# SWD.net
KiCad netlist of a schematic drawn in Altium Designer
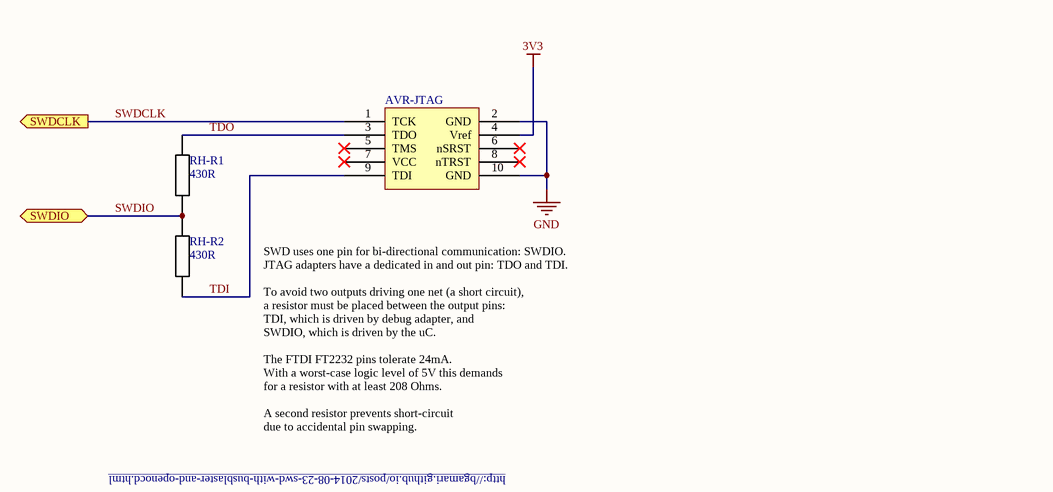
[diagram p0: SWD.SchDoc]

(export (version "E")
  (design (tool "Eeschema 10.0.6"))
  (components
    (comp (ref "AVR-JTAG")
      (value "AVR Style")
      (footprint "Header 2x5 IDC-10S")
      (libsource (lib "Headers") (part "Header JTAG AVR"))
    )
    (comp (ref "RH-R1")
      (value "430R")
      (footprint "R 0805 / 2012")
      (libsource (lib "Core51822-related") (part "Resistor"))
    )
    (comp (ref "RH-R2")
      (value "430R")
      (footprint "R 0805 / 2012")
      (libsource (lib "Core51822-related") (part "Resistor"))
    )
  )
  (nets
    (net (code "1") (name "/SWDCLK") (class "Default")
      (node (ref "AVR-JTAG") (pin "1") (pinfunction "TCK_1") (pintype "passive"))
    )
    (net (code "2") (name "/SWDIO") (class "Default")
      (node (ref "RH-R1") (pin "1") (pinfunction "1_1") (pintype "passive"))
      (node (ref "RH-R2") (pin "2") (pinfunction "2_2") (pintype "passive"))
    )
    (net (code "3") (name "/TDI") (class "Default")
      (node (ref "AVR-JTAG") (pin "9") (pinfunction "TDI_9") (pintype "passive"))
      (node (ref "RH-R2") (pin "1") (pinfunction "1_1") (pintype "passive"))
    )
    (net (code "4") (name "/TDO") (class "Default")
      (node (ref "AVR-JTAG") (pin "3") (pinfunction "TDO_3") (pintype "passive"))
      (node (ref "RH-R1") (pin "2") (pinfunction "2_2") (pintype "passive"))
    )
    (net (code "5") (name "3V3") (class "Default")
      (node (ref "AVR-JTAG") (pin "4") (pinfunction "Vref_4") (pintype "passive"))
    )
    (net (code "6") (name "GND") (class "Default")
      (node (ref "AVR-JTAG") (pin "10") (pinfunction "GND_10") (pintype "passive"))
      (node (ref "AVR-JTAG") (pin "2") (pinfunction "GND_2") (pintype "passive"))
    )
    (net (code "7") (name "unconnected-(AVR-JTAG-TMS-Pad5)") (class "Default")
      (node (ref "AVR-JTAG") (pin "5") (pinfunction "TMS_5") (pintype "passive+no_connect"))
    )
    (net (code "8") (name "unconnected-(AVR-JTAG-VCC-Pad7)") (class "Default")
      (node (ref "AVR-JTAG") (pin "7") (pinfunction "VCC_7") (pintype "passive+no_connect"))
    )
    (net (code "9") (name "unconnected-(AVR-JTAG-nSRST-Pad6)") (class "Default")
      (node (ref "AVR-JTAG") (pin "6") (pinfunction "nSRST_6") (pintype "passive+no_connect"))
    )
    (net (code "10") (name "unconnected-(AVR-JTAG-nTRST-Pad8)") (class "Default")
      (node (ref "AVR-JTAG") (pin "8") (pinfunction "nTRST_8") (pintype "passive+no_connect"))
    )
  )
)
